# Controller.net
KiCad netlist of a schematic drawn in Altium Designer
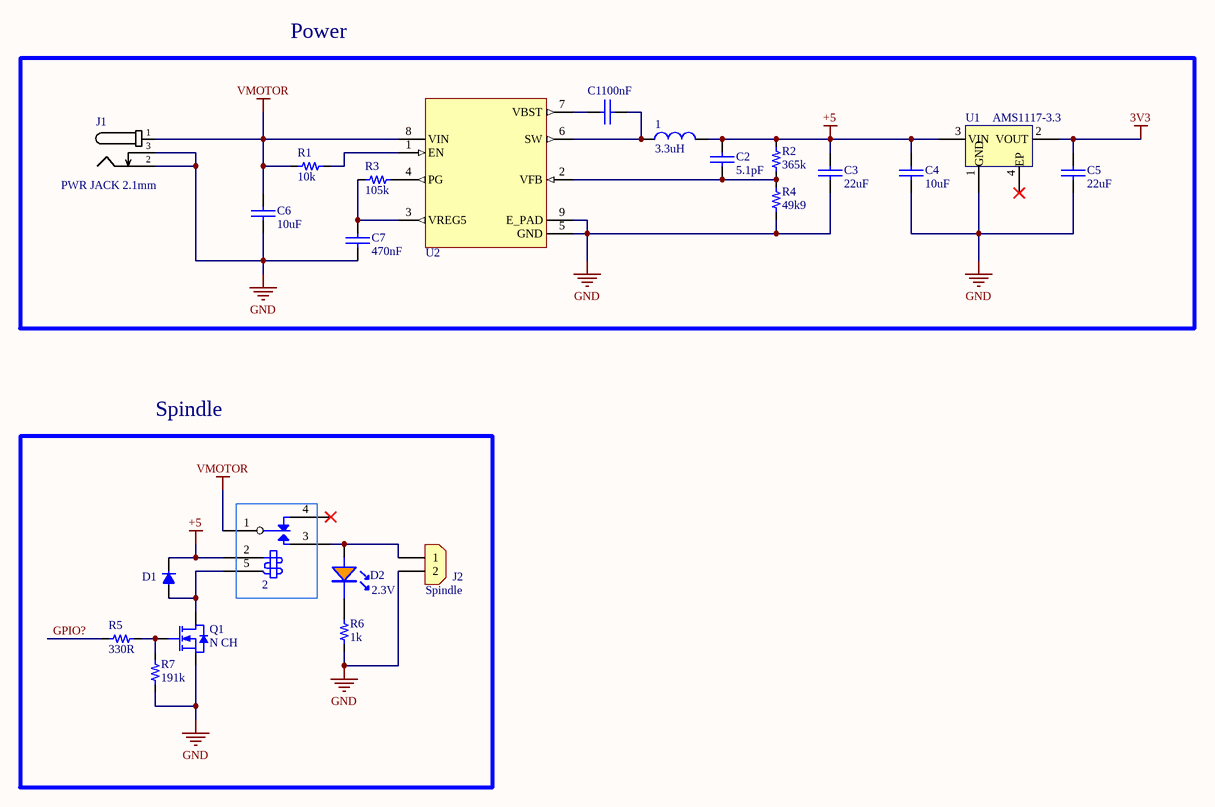
[diagram p0: Controller.SchDoc]

(export (version "E")
  (design (tool "Eeschema 10.0.6"))
  (components
    (comp (ref "1")
      (value "3.3uH")
      (footprint "Ind_5.8*5.2_NS")
      (description "2.6A 3.3uH Magnetic Shielded Inductor ±20% 3.6A 52mΩ SMD,4x4mm Fixed Inductors RoHS")
      (fields
        (field (name "MANUFACTURER") "cjiang")
        (field (name "MANUFACTURER PART NUMBER") "FNR4030S3R3MT")
      )
      (libsource (lib "CNCLib") (part "Inductor_3.3uH"))
    )
    (comp (ref "2")
      (value "V_15A")
      (footprint "Relay_5V_15A")
      (description "250V@AC 5V 15A 1 Form C: 1C (SPDT-CO) Plugin,15.6x19.2mm Power Relays ROHS")
      (fields
        (field (name "MANUFACTURER") "Ningbo Songle Relay")
        (field (name "MANUFACTURER PART NUMBER") "SRD-05VDC-SL-C")
      )
      (libsource (lib "CNCLib") (part "Relay_5V_15A"))
    )
    (comp (ref "C1")
      (value "100nF")
      (footprint "0603_cap")
      (description "50V 100nF X7R ±10% 0603 Ceramic Capacitors RoHS")
      (fields
        (field (name "MANUFACTURER") "FOJAN")
        (field (name "MANUFACTURER PART NUMBER") "FCC0603B104K500CT")
      )
      (libsource (lib "CNCLib") (part "Cap_100nF_0603_50V"))
    )
    (comp (ref "C2")
      (value "5.1pF")
      (footprint "0603_cap")
      (description "50V 5.1pF NP0 0603 Ceramic Capacitors RoHS")
      (fields
        (field (name "MANUFACTURER") "YAGEO")
        (field (name "MANUFACTURER PART NUMBER") "CC0603CRNPO9BN5R1")
      )
      (libsource (lib "CNCLib") (part "Cap_5.1pF"))
    )
    (comp (ref "C3")
      (value "22uF")
      (footprint "0603_cap")
      (description "10V 22uF X5R ±20% 0603 Multilayer Ceramic Capacitors MLCC - SMD/SMT ROHS")
      (fields
        (field (name "MANUFACTURER") "HRE")
        (field (name "MANUFACTURER PART NUMBER") "CGA0603X5R226M100JT")
      )
      (libsource (lib "CNCLib") (part "Cap_22uF_0603_10V"))
    )
    (comp (ref "C4")
      (value "10uF")
      (footprint "0603_cap")
      (description "10V 10uF X5R ±10% 0603 Multilayer Ceramic Capacitors MLCC - SMD/SMT ROHS")
      (fields
        (field (name "MANUFACTURER") "CCTC")
        (field (name "MANUFACTURER PART NUMBER") "TCC0603X5R106K100CT")
      )
      (libsource (lib "CNCLib") (part "Cap_10uF_0603_10V"))
    )
    (comp (ref "C5")
      (value "22uF")
      (footprint "0603_cap")
      (description "10V 22uF X5R ±20% 0603 Multilayer Ceramic Capacitors MLCC - SMD/SMT ROHS")
      (fields
        (field (name "MANUFACTURER") "HRE")
        (field (name "MANUFACTURER PART NUMBER") "CGA0603X5R226M100JT")
      )
      (libsource (lib "CNCLib") (part "Cap_22uF_0603_10V"))
    )
    (comp (ref "C6")
      (value "10uF")
      (description "25V 10uF X5R ±10% 0805 Multilayer Ceramic Capacitors MLCC - SMD/SMT ROHS")
      (fields
        (field (name "MANUFACTURER") "Samsung Electro-Mechanics")
        (field (name "MANUFACTURER PART NUMBER") "CL21A106KAYNNNE")
      )
      (libsource (lib "CNCLib") (part "Cap_10uF_0805_25V_"))
    )
    (comp (ref "C7")
      (value "470nF")
      (footprint "0603_cap")
      (description "50V 470nF X7R ±10% 0603 Multilayer Ceramic Capacitors MLCC - SMD/SMT ROHS")
      (fields
        (field (name "MANUFACTURER") "Chinocera")
        (field (name "MANUFACTURER PART NUMBER") "HGC0603R7474K500NTHJ")
      )
      (libsource (lib "CNCLib") (part "Cap_470nF_0603_50V"))
    )
    (comp (ref "D1")
      (value "DIODE STANDARD 50V 1A SOD-123F")
      (description "25A Independent 50V 1.1V@1A 1A SOD-123F Single Diodes RoHS")
      (fields (field (name "MANUFACTURER") "YONGYUTAI") (field (name "MANUFACTURER PART NUMBER") "1N4001W"))
      (libsource (lib "CNCLib") (part "1N4001W"))
    )
    (comp (ref "D2")
      (value "2.3V")
      (footprint "0805_LED")
      (description "LED ORANGE WATER CLEAR 0805 SMD")
      (fields
        (field (name "MANUFACTURER") "XINGLIGHT")
        (field (name "MANUFACTURER PART NUMBER") "XL-2012UOC")
      )
      (libsource (lib "CNCLib") (part "LED_0805_Orange"))
    )
    (comp (ref "J1")
      (value "PWR JACK 2.1mm")
      (footprint "CON_POWER_BARREL_2.1MM_3CONN")
      (description "CONN PWR JACK 2X5.5MM SOLDER")
      (fields (field (name "MANUFACTURER") "HCTL") (field (name "MANUFACTURER PART NUMBER") "HC-DC-005-2.0T"))
      (libsource (lib "CNCLib") (part "Con_Power_Jack_2.1mm_3pins"))
    )
    (comp (ref "J2")
      (value "Connector 2pos")
      (footprint "CON_2x1_TH_5MM")
      (description "2POS 5MM")
      (fields (field (name "MANUFACTURER") "JILN") (field (name "MANUFACTURER PART NUMBER") "JL126-50002G01"))
      (libsource (lib "CNCLib") (part "Con_2x1_TH_5mm"))
    )
    (comp (ref "Q1")
      (value "N CH")
      (footprint "SOT_23_3")
      (description "MOSFET N-CH 20V SOT23")
      (fields (field (name "MANUFACTURER") "Doeshare") (field (name "MANUFACTURER PART NUMBER") "DN2302S"))
      (libsource (lib "CNCLib") (part "Q_NFET_20V_3.2A_SOT23"))
    )
    (comp (ref "R1")
      (value "10k")
      (footprint "0603_res")
      (description "RES SMD 10k OHM 5% 1/10W 0603")
      (fields (field (name "MANUFACTURER") "FOJAN") (field (name "MANUFACTURER PART NUMBER") "FRC0603J103TS"))
      (libsource (lib "CNCLib") (part "Res_10k_0603_1/10W"))
    )
    (comp (ref "R2")
      (value "365k")
      (footprint "0603_res")
      (description "100mW Thick Film Resistor 75V ±100ppm/℃ ±1% 365kΩ 0603 Chip Resistor - Surface Mount ROHS")
      (fields
        (field (name "MANUFACTURER") "YAGEO")
        (field (name "MANUFACTURER PART NUMBER") "RC0603FR-07365KL")
      )
      (libsource (lib "CNCLib") (part "Res_365k_0603_1/10W"))
    )
    (comp (ref "R3")
      (value "105k")
      (footprint "0603_res")
      (description "100mW 105kΩ 75V ±25ppm/℃ Thin Film Resistor ±0.5% 0603 Chip Resistor - Surface Mount RoHS")
      (fields
        (field (name "MANUFACTURER") "YAGEO")
        (field (name "MANUFACTURER PART NUMBER") "RT0603DRD07105KL")
      )
      (libsource (lib "CNCLib") (part "Res 105k"))
    )
    (comp (ref "R4")
      (value "49k9")
      (footprint "0603_res")
      (description "100mW Thick Film Resistor 75V ±100ppm/℃ ±1% 49.9kΩ 0603 Chip Resistor - Surface Mount ROHS")
      (fields
        (field (name "MANUFACTURER") "YAGEO")
        (field (name "MANUFACTURER PART NUMBER") "RC0603FR-0749K9L")
      )
      (libsource (lib "CNCLib") (part "Res_49k9_0603_1/10W"))
    )
    (comp (ref "R5")
      (value "330R")
      (footprint "0603_res")
      (description "RES SMD 330R OHM 5% 1/10W 0603")
      (fields
        (field (name "MANUFACTURER") "FOJAN")
        (field (name "MANUFACTURER PART NUMBER") "FRC0603J331 TS")
      )
      (libsource (lib "CNCLib") (part "Res_330R_0603_1/10W"))
    )
    (comp (ref "R6")
      (value "1k")
      (footprint "0603_res")
      (description "RES SMD 1k OHM 5% 1/10W 0603")
      (fields
        (field (name "MANUFACTURER") "FOJAN")
        (field (name "MANUFACTURER PART NUMBER") "FRC0603J102 TS")
      )
      (libsource (lib "CNCLib") (part "Res_1k_0603_1/10W"))
    )
    (comp (ref "R7")
      (value "191k")
      (footprint "0603_res")
      (description "100mW Thick Film Resistor 75V ±100ppm/℃ ±1% 191kΩ 0603 Chip Resistor - Surface Mount ROHS")
      (fields
        (field (name "MANUFACTURER") "YAGEO")
        (field (name "MANUFACTURER PART NUMBER") "AC0603FR-07191KL")
      )
      (libsource (lib "CNCLib") (part "Res_191k_0603_1/10W"))
    )
    (comp (ref "U1")
      (value "AMS1117-3.3")
      (footprint "SOT_223")
      (description "1A 60dB@(120Hz) Fixed 3.3V Positive 18V SOT-223 Linear Voltage Regulators (LDO) ROHS")
      (fields (field (name "MANUFACTURER") "UMW(Youtai Semiconductor Co., Ltd.)"))
      (libsource (lib "CNCLib") (part "LDO_3V3_1A_FIXED"))
    )
    (comp (ref "U2")
      (value "TPS56528DDAR")
      (footprint "SOIC_8_3.9mm_EP")
      (description "IC REG BUCK ADJ 5A 8SOPWR")
      (fields (field (name "MANUFACTURER") "Texas Instruments"))
      (libsource (lib "CNCLib") (part "DCDC_SW_BUCK_5A_SOIC8"))
    )
  )
  (nets
    (net (code "1") (name "+5") (class "Default")
      (node (ref "1") (pin "2") (pinfunction "2_2") (pintype "passive"))
      (node (ref "2") (pin "2") (pinfunction "2_2") (pintype "passive"))
      (node (ref "C2") (pin "1") (pinfunction "1_1") (pintype "passive"))
      (node (ref "C3") (pin "1") (pinfunction "1_1") (pintype "passive"))
      (node (ref "C4") (pin "1") (pinfunction "1_1") (pintype "passive"))
      (node (ref "D1") (pin "2") (pinfunction "CATHODE_2") (pintype "passive"))
      (node (ref "R2") (pin "2") (pinfunction "2_2") (pintype "passive"))
      (node (ref "U1") (pin "3") (pinfunction "VIN_3") (pintype "passive"))
    )
    (net (code "2") (name "/GPIO?") (class "Default")
      (node (ref "R5") (pin "1") (pinfunction "1_1") (pintype "passive"))
    )
    (net (code "3") (name "3V3") (class "Default")
      (node (ref "C5") (pin "1") (pinfunction "1_1") (pintype "passive"))
      (node (ref "U1") (pin "2") (pinfunction "VOUT_2") (pintype "passive"))
    )
    (net (code "4") (name "GND") (class "Default")
      (node (ref "C3") (pin "2") (pinfunction "2_2") (pintype "passive"))
      (node (ref "C4") (pin "2") (pinfunction "2_2") (pintype "passive"))
      (node (ref "C5") (pin "2") (pinfunction "2_2") (pintype "passive"))
      (node (ref "C6") (pin "2") (pinfunction "2_2") (pintype "passive"))
      (node (ref "C7") (pin "2") (pinfunction "2_2") (pintype "passive"))
      (node (ref "J1") (pin "2") (pinfunction "2_2") (pintype "passive"))
      (node (ref "J1") (pin "3") (pinfunction "3_3") (pintype "passive"))
      (node (ref "J2") (pin "2") (pinfunction "2_2") (pintype "passive"))
      (node (ref "Q1") (pin "2") (pinfunction "S_2") (pintype "passive"))
      (node (ref "R4") (pin "1") (pinfunction "1_1") (pintype "passive"))
      (node (ref "R6") (pin "1") (pinfunction "1_1") (pintype "passive"))
      (node (ref "R7") (pin "2") (pinfunction "2_2") (pintype "passive"))
      (node (ref "U1") (pin "1") (pinfunction "GND_1") (pintype "passive"))
      (node (ref "U2") (pin "5") (pinfunction "GND_5") (pintype "power_in"))
      (node (ref "U2") (pin "9") (pinfunction "E_PAD_9") (pintype "power_in"))
    )
    (net (code "5") (name "Net-(D1-ANODE)") (class "Default")
      (node (ref "2") (pin "5") (pinfunction "5_5") (pintype "passive"))
      (node (ref "D1") (pin "1") (pinfunction "ANODE_1") (pintype "passive"))
      (node (ref "Q1") (pin "3") (pinfunction "D_3") (pintype "passive"))
    )
    (net (code "6") (name "Net-(D2-A)") (class "Default")
      (node (ref "2") (pin "3") (pinfunction "3_3") (pintype "passive"))
      (node (ref "D2") (pin "1") (pinfunction "A_1") (pintype "passive"))
      (node (ref "J2") (pin "1") (pinfunction "1_1") (pintype "passive"))
    )
    (net (code "7") (name "Net-(D2-Pad2)") (class "Default")
      (node (ref "D2") (pin "2") (pinfunction "2_2") (pintype "passive"))
      (node (ref "R6") (pin "2") (pinfunction "2_2") (pintype "passive"))
    )
    (net (code "8") (name "Net-(Q1-G)") (class "Default")
      (node (ref "Q1") (pin "1") (pinfunction "G_1") (pintype "passive"))
      (node (ref "R5") (pin "2") (pinfunction "2_2") (pintype "passive"))
      (node (ref "R7") (pin "1") (pinfunction "1_1") (pintype "passive"))
    )
    (net (code "9") (name "Net-(U2-EN)") (class "Default")
      (node (ref "R1") (pin "2") (pinfunction "2_2") (pintype "passive"))
      (node (ref "U2") (pin "1") (pinfunction "EN_1") (pintype "input"))
    )
    (net (code "10") (name "Net-(U2-PG)") (class "Default")
      (node (ref "R3") (pin "2") (pinfunction "2_2") (pintype "passive"))
      (node (ref "U2") (pin "4") (pinfunction "PG_4") (pintype "output"))
    )
    (net (code "11") (name "Net-(U2-SW)") (class "Default")
      (node (ref "1") (pin "1") (pinfunction "1_1") (pintype "passive"))
      (node (ref "C1") (pin "1") (pinfunction "1_1") (pintype "passive"))
      (node (ref "U2") (pin "6") (pinfunction "SW_6") (pintype "output"))
    )
    (net (code "12") (name "Net-(U2-VBST)") (class "Default")
      (node (ref "C1") (pin "2") (pinfunction "2_2") (pintype "passive"))
      (node (ref "U2") (pin "7") (pinfunction "VBST_7") (pintype "output"))
    )
    (net (code "13") (name "Net-(U2-VFB)") (class "Default")
      (node (ref "C2") (pin "2") (pinfunction "2_2") (pintype "passive"))
      (node (ref "R2") (pin "1") (pinfunction "1_1") (pintype "passive"))
      (node (ref "R4") (pin "2") (pinfunction "2_2") (pintype "passive"))
      (node (ref "U2") (pin "2") (pinfunction "VFB_2") (pintype "input"))
    )
    (net (code "14") (name "Net-(U2-VREG5)") (class "Default")
      (node (ref "C7") (pin "1") (pinfunction "1_1") (pintype "passive"))
      (node (ref "R3") (pin "1") (pinfunction "1_1") (pintype "passive"))
      (node (ref "U2") (pin "3") (pinfunction "VREG5_3") (pintype "output"))
    )
    (net (code "15") (name "VMOTOR") (class "Default")
      (node (ref "2") (pin "1") (pinfunction "1_1") (pintype "passive"))
      (node (ref "C6") (pin "1") (pinfunction "1_1") (pintype "passive"))
      (node (ref "J1") (pin "1") (pinfunction "1_1") (pintype "passive"))
      (node (ref "R1") (pin "1") (pinfunction "1_1") (pintype "passive"))
      (node (ref "U2") (pin "8") (pinfunction "VIN_8") (pintype "power_in"))
    )
    (net (code "16") (name "unconnected-(2-Pad4)") (class "Default")
      (node (ref "2") (pin "4") (pinfunction "4_4") (pintype "passive+no_connect"))
    )
    (net (code "17") (name "unconnected-(U1-EP-Pad4)") (class "Default")
      (node (ref "U1") (pin "4") (pinfunction "EP_4") (pintype "passive+no_connect"))
    )
  )
)
